# SCH_AP_tempboard_2024-01-17.net
KiCad netlist of a schematic drawn in EasyEDA
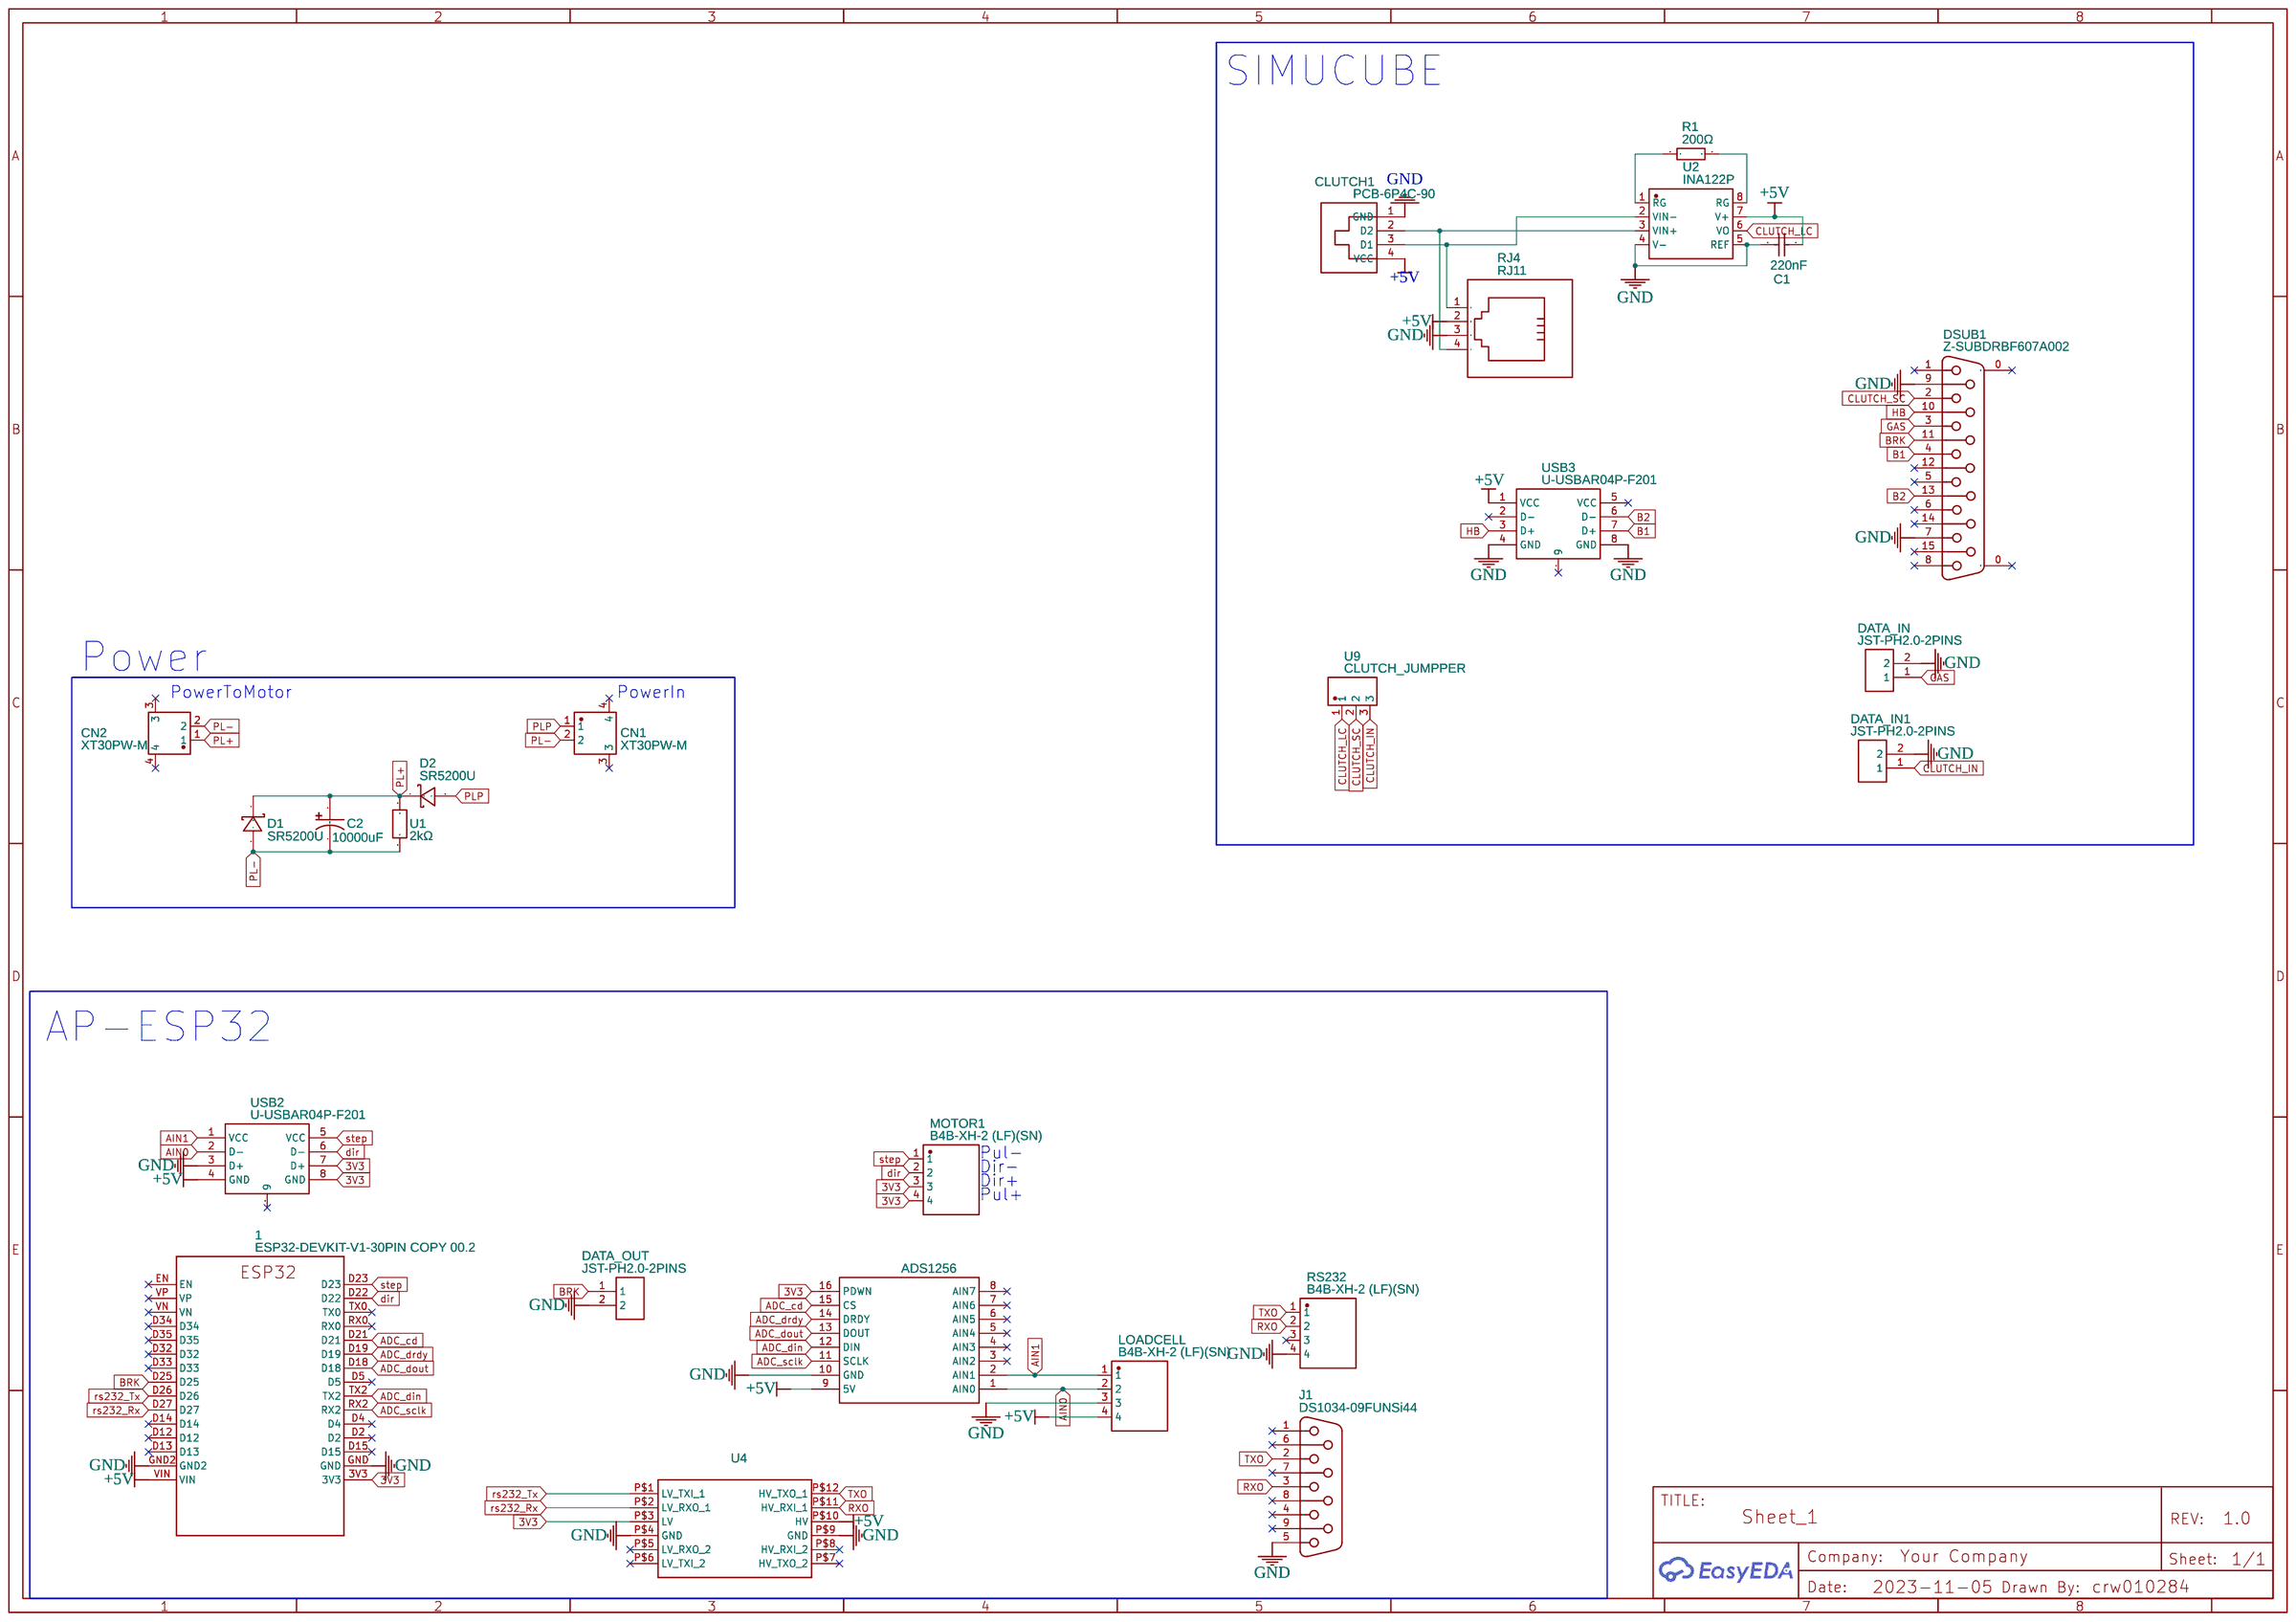
[diagram p0: schematic sheet]

(export (version "E")
  (design (tool "Eeschema 10.0.6"))
  (components
    (comp (ref "1")
      (value "ESP32-DEVKIT-V1-30PIN COPY 00.2")
      (libsource (lib "") (part "ESP32-DEVKIT-V1-30PIN"))
    )
    (comp (ref "C1")
      (value "220nF")
      (fields
        (field (name "Manufacturer Part") "CL10B224KA8NNNC")
        (field (name "Manufacturer") "SAMSUNG(三星)")
      )
      (libsource (lib "") (part "CL10B224KA8NNNC"))
    )
    (comp (ref "C2")
      (value "10000uF")
      (fields (field (name "Manufacturer Part") "HL103M063O510A") (field (name "Manufacturer") "CapXon(丰宾)"))
      (libsource (lib "") (part "HL103M063O510A"))
    )
    (comp (ref "CLUTCH1")
      (value "PCB-6P4C-90")
      (fields (field (name "Manufacturer Part") "R-RJ11R04P-A800") (field (name "Manufacturer") "Ckmtw(灿科盟)"))
      (libsource (lib "") (part "PCB-6P4C-90"))
    )
    (comp (ref "CN1")
      (value "XT30PW-M")
      (fields (field (name "Manufacturer") "AMASS(艾迈斯)"))
      (libsource (lib "") (part "XT30PW-M_1"))
    )
    (comp (ref "CN2")
      (value "XT30PW-M")
      (fields (field (name "Manufacturer") "AMASS(艾迈斯)"))
      (libsource (lib "") (part "XT30PW-M"))
    )
    (comp (ref "D1")
      (value "SR5200U")
      (fields (field (name "Manufacturer") "迪一"))
      (libsource (lib "") (part "SR5200U_1"))
    )
    (comp (ref "D2")
      (value "SR5200U")
      (fields (field (name "Manufacturer") "迪一"))
      (libsource (lib "") (part "SR5200U"))
    )
    (comp (ref "DATA_IN") (value "JST-PH2.0-2PINS") (libsource (lib "") (part "JST-PH2.0-2PINS")))
    (comp (ref "DATA_IN1") (value "JST-PH2.0-2PINS") (libsource (lib "") (part "JST-PH2.0-2PINS")))
    (comp (ref "DATA_OUT") (value "JST-PH2.0-2PINS") (libsource (lib "") (part "JST-PH2.0-2PINS_1")))
    (comp (ref "DSUB1")
      (value "Z-SUBDRBF607A002")
      (fields (field (name "Manufacturer") "Nextron(台湾正凌)"))
      (libsource (lib "") (part "Z-SUBDRBF607A002"))
    )
    (comp (ref "J1")
      (value "DS1034-09FUNSi44")
      (fields (field (name "Manufacturer") "CONNFLY"))
      (libsource (lib "") (part "DS1034-09FUNSi44"))
    )
    (comp (ref "LOADCELL")
      (value "B4B-XH-2 (LF)(SN)")
      (fields (field (name "Manufacturer Part") "B4B-XH-2(LF)(SN)") (field (name "Manufacturer") "JST"))
      (libsource (lib "") (part "B4B-XH-2 (LF)(SN)_2"))
    )
    (comp (ref "MOTOR1")
      (value "B4B-XH-2 (LF)(SN)")
      (fields (field (name "Manufacturer Part") "B4B-XH-2(LF)(SN)") (field (name "Manufacturer") "JST"))
      (libsource (lib "") (part "B4B-XH-2 (LF)(SN)"))
    )
    (comp (ref "R1")
      (value "200Ω")
      (fields
        (field (name "Manufacturer Part") "0402WGF2000TCE")
        (field (name "Manufacturer") "UNI-ROYAL(厚声)")
      )
      (libsource (lib "") (part "0402WGF2000TCE"))
    )
    (comp (ref "RJ4")
      (value "RJ11")
      (fields
        (field (name "Manufacturer Part") "RJII-623K-4P4CGray boundless")
        (field (name "Manufacturer") "ReliaPro")
      )
      (libsource (lib "") (part "RJII-623K-4P4CGray boundless"))
    )
    (comp (ref "RS232")
      (value "B4B-XH-2 (LF)(SN)")
      (fields (field (name "Manufacturer Part") "B4B-XH-2(LF)(SN)") (field (name "Manufacturer") "JST"))
      (libsource (lib "") (part "B4B-XH-2 (LF)(SN)_1"))
    )
    (comp (ref "U1")
      (value "2kΩ")
      (fields (field (name "Manufacturer Part") "RSF5WSJB-91-2K") (field (name "Manufacturer") "YAGEO(国巨)"))
      (libsource (lib "") (part "RSF5WSJB-91-2K"))
    )
    (comp (ref "U2")
      (value "INA122P")
      (fields (field (name "Manufacturer") "TI(德州仪器)"))
      (libsource (lib "") (part "INA122P"))
    )
    (comp (ref "U3") (value "ADS1256") (libsource (lib "") (part "ADS1256")))
    (comp (ref "U4") (value "NO") (libsource (lib "") (part "LOGIC_LEVEL_CONVERTER")))
    (comp (ref "U9")
      (value "CLUTCH_JUMPPER")
      (fields (field (name "Manufacturer Part") "Jumper3"))
      (libsource (lib "") (part "JUMPER3"))
    )
    (comp (ref "USB2")
      (value "U-USBAR04P-F201")
      (fields (field (name "Manufacturer") "Ckmtw(灿科盟)"))
      (libsource (lib "") (part "U-USBAR04P-F201"))
    )
    (comp (ref "USB3")
      (value "U-USBAR04P-F201")
      (fields (field (name "Manufacturer") "Ckmtw(灿科盟)"))
      (libsource (lib "") (part "U-USBAR04P-F201"))
    )
  )
  (nets
    (net (code "1") (name "+5V") (class "Default")
      (node (ref "1") (pin "VIN") (pinfunction "VIN_VIN") (pintype "unspecified"))
      (node (ref "C1") (pin "2") (pinfunction "2_2") (pintype "input"))
      (node (ref "CLUTCH1") (pin "4") (pinfunction "VCC_4") (pintype "unspecified"))
      (node (ref "LOADCELL") (pin "4") (pinfunction "4_4") (pintype "unspecified"))
      (node (ref "RJ4") (pin "2") (pinfunction "2_2") (pintype "unspecified"))
      (node (ref "U2") (pin "7") (pinfunction "V+_7") (pintype "unspecified"))
      (node (ref "U3") (pin "9") (pinfunction "5V_9") (pintype "unspecified"))
      (node (ref "U4") (pin "P$10") (pinfunction "HV_P$10") (pintype "unspecified"))
      (node (ref "USB2") (pin "4") (pinfunction "GND_4") (pintype "unspecified"))
      (node (ref "USB3") (pin "1") (pinfunction "VCC_1") (pintype "unspecified"))
    )
    (net (code "2") (name "3V3") (class "Default")
      (node (ref "1") (pin "3V3") (pinfunction "3V3_3V3") (pintype "unspecified"))
      (node (ref "MOTOR1") (pin "3") (pinfunction "3_3") (pintype "unspecified"))
      (node (ref "MOTOR1") (pin "4") (pinfunction "4_4") (pintype "unspecified"))
      (node (ref "U3") (pin "16") (pinfunction "PDWN_16") (pintype "unspecified"))
      (node (ref "U4") (pin "P$3") (pinfunction "LV_P$3") (pintype "unspecified"))
      (node (ref "USB2") (pin "7") (pinfunction "D+_7") (pintype "unspecified"))
      (node (ref "USB2") (pin "8") (pinfunction "GND_8") (pintype "unspecified"))
    )
    (net (code "3") (name "ADC_cd") (class "Default")
      (node (ref "1") (pin "D21") (pinfunction "D21_D21") (pintype "unspecified"))
      (node (ref "U3") (pin "15") (pinfunction "CS_15") (pintype "unspecified"))
    )
    (net (code "4") (name "ADC_din") (class "Default")
      (node (ref "1") (pin "TX2") (pinfunction "TX2_TX2") (pintype "unspecified"))
      (node (ref "U3") (pin "12") (pinfunction "DIN_12") (pintype "unspecified"))
    )
    (net (code "5") (name "ADC_dout") (class "Default")
      (node (ref "1") (pin "D18") (pinfunction "D18_D18") (pintype "unspecified"))
      (node (ref "U3") (pin "13") (pinfunction "DOUT_13") (pintype "unspecified"))
    )
    (net (code "6") (name "ADC_drdy") (class "Default")
      (node (ref "1") (pin "D19") (pinfunction "D19_D19") (pintype "unspecified"))
      (node (ref "U3") (pin "14") (pinfunction "DRDY_14") (pintype "unspecified"))
    )
    (net (code "7") (name "ADC_sclk") (class "Default")
      (node (ref "1") (pin "RX2") (pinfunction "RX2_RX2") (pintype "unspecified"))
      (node (ref "U3") (pin "11") (pinfunction "SCLK_11") (pintype "unspecified"))
    )
    (net (code "8") (name "AIN0") (class "Default")
      (node (ref "LOADCELL") (pin "2") (pinfunction "2_2") (pintype "unspecified"))
      (node (ref "U3") (pin "1") (pinfunction "AIN0_1") (pintype "unspecified"))
      (node (ref "USB2") (pin "2") (pinfunction "D-_2") (pintype "unspecified"))
    )
    (net (code "9") (name "AIN1") (class "Default")
      (node (ref "LOADCELL") (pin "1") (pinfunction "1_1") (pintype "unspecified"))
      (node (ref "U3") (pin "2") (pinfunction "AIN1_2") (pintype "unspecified"))
      (node (ref "USB2") (pin "1") (pinfunction "VCC_1") (pintype "unspecified"))
    )
    (net (code "10") (name "B1") (class "Default")
      (node (ref "DSUB1") (pin "4") (pinfunction "4_4") (pintype "input"))
      (node (ref "USB3") (pin "7") (pinfunction "D+_7") (pintype "unspecified"))
    )
    (net (code "11") (name "B2") (class "Default")
      (node (ref "DSUB1") (pin "13") (pinfunction "13_13") (pintype "input"))
      (node (ref "USB3") (pin "6") (pinfunction "D-_6") (pintype "unspecified"))
    )
    (net (code "12") (name "BRK") (class "Default")
      (node (ref "1") (pin "D25") (pinfunction "D25_D25") (pintype "unspecified"))
      (node (ref "DATA_OUT") (pin "1") (pinfunction "1_1") (pintype "unspecified"))
      (node (ref "DSUB1") (pin "11") (pinfunction "11_11") (pintype "input"))
    )
    (net (code "13") (name "CLUTCH_IN") (class "Default")
      (node (ref "DATA_IN1") (pin "1") (pinfunction "1_1") (pintype "unspecified"))
      (node (ref "U9") (pin "3") (pinfunction "3_3") (pintype "unspecified"))
    )
    (net (code "14") (name "CLUTCH_LC") (class "Default")
      (node (ref "U2") (pin "6") (pinfunction "VO_6") (pintype "unspecified"))
      (node (ref "U9") (pin "1") (pinfunction "1_1") (pintype "unspecified"))
    )
    (net (code "15") (name "CLUTCH_SC") (class "Default")
      (node (ref "DSUB1") (pin "2") (pinfunction "2_2") (pintype "input"))
      (node (ref "U9") (pin "2") (pinfunction "2_2") (pintype "unspecified"))
    )
    (net (code "16") (name "GAS") (class "Default")
      (node (ref "DATA_IN") (pin "1") (pinfunction "1_1") (pintype "unspecified"))
      (node (ref "DSUB1") (pin "3") (pinfunction "3_3") (pintype "input"))
    )
    (net (code "17") (name "GND") (class "Default")
      (node (ref "1") (pin "GND") (pinfunction "GND_GND") (pintype "unspecified"))
      (node (ref "1") (pin "GND2") (pinfunction "GND2_GND2") (pintype "unspecified"))
      (node (ref "C1") (pin "1") (pinfunction "1_1") (pintype "input"))
      (node (ref "CLUTCH1") (pin "1") (pinfunction "GND_1") (pintype "unspecified"))
      (node (ref "DATA_IN") (pin "2") (pinfunction "2_2") (pintype "unspecified"))
      (node (ref "DATA_IN1") (pin "2") (pinfunction "2_2") (pintype "unspecified"))
      (node (ref "DATA_OUT") (pin "2") (pinfunction "2_2") (pintype "unspecified"))
      (node (ref "DSUB1") (pin "7") (pinfunction "7_7") (pintype "input"))
      (node (ref "DSUB1") (pin "9") (pinfunction "9_9") (pintype "input"))
      (node (ref "J1") (pin "5") (pinfunction "5_5") (pintype "unspecified"))
      (node (ref "LOADCELL") (pin "3") (pinfunction "3_3") (pintype "unspecified"))
      (node (ref "RJ4") (pin "3") (pinfunction "3_3") (pintype "unspecified"))
      (node (ref "RS232") (pin "4") (pinfunction "4_4") (pintype "unspecified"))
      (node (ref "U2") (pin "4") (pinfunction "V-_4") (pintype "unspecified"))
      (node (ref "U2") (pin "5") (pinfunction "REF_5") (pintype "unspecified"))
      (node (ref "U3") (pin "10") (pinfunction "GND_10") (pintype "unspecified"))
      (node (ref "U4") (pin "P$4") (pinfunction "GND_P$4") (pintype "unspecified"))
      (node (ref "U4") (pin "P$9") (pinfunction "GND_P$9") (pintype "unspecified"))
      (node (ref "USB2") (pin "3") (pinfunction "D+_3") (pintype "unspecified"))
      (node (ref "USB3") (pin "4") (pinfunction "GND_4") (pintype "unspecified"))
      (node (ref "USB3") (pin "8") (pinfunction "GND_8") (pintype "unspecified"))
    )
    (net (code "18") (name "HB") (class "Default")
      (node (ref "DSUB1") (pin "10") (pinfunction "10_10") (pintype "input"))
      (node (ref "USB3") (pin "3") (pinfunction "D+_3") (pintype "unspecified"))
    )
    (net (code "19") (name "Net-(CLUTCH1-D1)") (class "Default")
      (node (ref "CLUTCH1") (pin "3") (pinfunction "D1_3") (pintype "unspecified"))
      (node (ref "RJ4") (pin "1") (pinfunction "1_1") (pintype "unspecified"))
      (node (ref "U2") (pin "2") (pinfunction "VIN-_2") (pintype "unspecified"))
    )
    (net (code "20") (name "Net-(CLUTCH1-D2)") (class "Default")
      (node (ref "CLUTCH1") (pin "2") (pinfunction "D2_2") (pintype "unspecified"))
      (node (ref "RJ4") (pin "4") (pinfunction "4_4") (pintype "unspecified"))
      (node (ref "U2") (pin "3") (pinfunction "VIN+_3") (pintype "unspecified"))
    )
    (net (code "21") (name "Net-(R1-Pad1)") (class "Default")
      (node (ref "R1") (pin "1") (pinfunction "1_1") (pintype "input"))
      (node (ref "U2") (pin "1") (pinfunction "RG_1") (pintype "unspecified"))
    )
    (net (code "22") (name "Net-(R1-Pad2)") (class "Default")
      (node (ref "R1") (pin "2") (pinfunction "2_2") (pintype "input"))
      (node (ref "U2") (pin "8") (pinfunction "RG_8") (pintype "unspecified"))
    )
    (net (code "23") (name "PL+") (class "Default")
      (node (ref "C2") (pin "1") (pinfunction "1_1") (pintype "unspecified"))
      (node (ref "CN2") (pin "1") (pinfunction "1_1") (pintype "unspecified"))
      (node (ref "D1") (pin "1") (pinfunction "C_1") (pintype "unspecified"))
      (node (ref "D2") (pin "1") (pinfunction "C_1") (pintype "unspecified"))
      (node (ref "U1") (pin "1") (pinfunction "1_1") (pintype "unspecified"))
    )
    (net (code "24") (name "PL-") (class "Default")
      (node (ref "C2") (pin "2") (pinfunction "2_2") (pintype "unspecified"))
      (node (ref "CN1") (pin "2") (pinfunction "2_2") (pintype "unspecified"))
      (node (ref "CN2") (pin "2") (pinfunction "2_2") (pintype "unspecified"))
      (node (ref "D1") (pin "2") (pinfunction "A_2") (pintype "unspecified"))
      (node (ref "U1") (pin "2") (pinfunction "2_2") (pintype "unspecified"))
    )
    (net (code "25") (name "PLP") (class "Default")
      (node (ref "CN1") (pin "1") (pinfunction "1_1") (pintype "unspecified"))
      (node (ref "D2") (pin "2") (pinfunction "A_2") (pintype "unspecified"))
    )
    (net (code "26") (name "RXO") (class "Default")
      (node (ref "J1") (pin "3") (pinfunction "3_3") (pintype "unspecified"))
      (node (ref "RS232") (pin "2") (pinfunction "2_2") (pintype "unspecified"))
      (node (ref "U4") (pin "P$11") (pinfunction "HV_RXI_1_P$11") (pintype "unspecified"))
    )
    (net (code "27") (name "TXO") (class "Default")
      (node (ref "J1") (pin "2") (pinfunction "2_2") (pintype "unspecified"))
      (node (ref "RS232") (pin "1") (pinfunction "1_1") (pintype "unspecified"))
      (node (ref "U4") (pin "P$12") (pinfunction "HV_TXO_1_P$12") (pintype "unspecified"))
    )
    (net (code "28") (name "dir") (class "Default")
      (node (ref "1") (pin "D22") (pinfunction "D22_D22") (pintype "unspecified"))
      (node (ref "MOTOR1") (pin "2") (pinfunction "2_2") (pintype "unspecified"))
      (node (ref "USB2") (pin "6") (pinfunction "D-_6") (pintype "unspecified"))
    )
    (net (code "29") (name "rs232_Rx") (class "Default")
      (node (ref "1") (pin "D27") (pinfunction "D27_D27") (pintype "unspecified"))
      (node (ref "U4") (pin "P$2") (pinfunction "LV_RXO_1_P$2") (pintype "unspecified"))
    )
    (net (code "30") (name "rs232_Tx") (class "Default")
      (node (ref "1") (pin "D26") (pinfunction "D26_D26") (pintype "unspecified"))
      (node (ref "U4") (pin "P$1") (pinfunction "LV_TXI_1_P$1") (pintype "unspecified"))
    )
    (net (code "31") (name "step") (class "Default")
      (node (ref "1") (pin "D23") (pinfunction "D23_D23") (pintype "unspecified"))
      (node (ref "MOTOR1") (pin "1") (pinfunction "1_1") (pintype "unspecified"))
      (node (ref "USB2") (pin "5") (pinfunction "VCC_5") (pintype "unspecified"))
    )
    (net (code "32") (name "unconnected-(1-PadD2)") (class "Default")
      (node (ref "1") (pin "D2") (pinfunction "D2_D2") (pintype "unspecified+no_connect"))
    )
    (net (code "33") (name "unconnected-(1-PadD4)") (class "Default")
      (node (ref "1") (pin "D4") (pinfunction "D4_D4") (pintype "unspecified+no_connect"))
    )
    (net (code "34") (name "unconnected-(1-PadD5)") (class "Default")
      (node (ref "1") (pin "D5") (pinfunction "D5_D5") (pintype "unspecified+no_connect"))
    )
    (net (code "35") (name "unconnected-(1-PadD12)") (class "Default")
      (node (ref "1") (pin "D12") (pinfunction "D12_D12") (pintype "unspecified+no_connect"))
    )
    (net (code "36") (name "unconnected-(1-PadD13)") (class "Default")
      (node (ref "1") (pin "D13") (pinfunction "D13_D13") (pintype "unspecified+no_connect"))
    )
    (net (code "37") (name "unconnected-(1-PadD14)") (class "Default")
      (node (ref "1") (pin "D14") (pinfunction "D14_D14") (pintype "unspecified+no_connect"))
    )
    (net (code "38") (name "unconnected-(1-PadD15)") (class "Default")
      (node (ref "1") (pin "D15") (pinfunction "D15_D15") (pintype "unspecified+no_connect"))
    )
    (net (code "39") (name "unconnected-(1-PadD32)") (class "Default")
      (node (ref "1") (pin "D32") (pinfunction "D32_D32") (pintype "unspecified+no_connect"))
    )
    (net (code "40") (name "unconnected-(1-PadD33)") (class "Default")
      (node (ref "1") (pin "D33") (pinfunction "D33_D33") (pintype "unspecified+no_connect"))
    )
    (net (code "41") (name "unconnected-(1-PadD34)") (class "Default")
      (node (ref "1") (pin "D34") (pinfunction "D34_D34") (pintype "unspecified+no_connect"))
    )
    (net (code "42") (name "unconnected-(1-PadD35)") (class "Default")
      (node (ref "1") (pin "D35") (pinfunction "D35_D35") (pintype "unspecified+no_connect"))
    )
    (net (code "43") (name "unconnected-(1-PadEN)") (class "Default")
      (node (ref "1") (pin "EN") (pinfunction "EN_EN") (pintype "unspecified+no_connect"))
    )
    (net (code "44") (name "unconnected-(1-PadRX0)") (class "Default")
      (node (ref "1") (pin "RX0") (pinfunction "RX0_RX0") (pintype "unspecified+no_connect"))
    )
    (net (code "45") (name "unconnected-(1-PadTX0)") (class "Default")
      (node (ref "1") (pin "TX0") (pinfunction "TX0_TX0") (pintype "unspecified+no_connect"))
    )
    (net (code "46") (name "unconnected-(1-PadVN)") (class "Default")
      (node (ref "1") (pin "VN") (pinfunction "VN_VN") (pintype "unspecified+no_connect"))
    )
    (net (code "47") (name "unconnected-(1-PadVP)") (class "Default")
      (node (ref "1") (pin "VP") (pinfunction "VP_VP") (pintype "unspecified+no_connect"))
    )
    (net (code "48") (name "unconnected-(CN1-Pad3)") (class "Default")
      (node (ref "CN1") (pin "3") (pinfunction "3_3") (pintype "unspecified+no_connect"))
    )
    (net (code "49") (name "unconnected-(CN1-Pad4)") (class "Default")
      (node (ref "CN1") (pin "4") (pinfunction "4_4") (pintype "unspecified+no_connect"))
    )
    (net (code "50") (name "unconnected-(CN2-Pad3)") (class "Default")
      (node (ref "CN2") (pin "3") (pinfunction "3_3") (pintype "unspecified+no_connect"))
    )
    (net (code "51") (name "unconnected-(CN2-Pad4)") (class "Default")
      (node (ref "CN2") (pin "4") (pinfunction "4_4") (pintype "unspecified+no_connect"))
    )
    (net (code "52") (name "unconnected-(DSUB1-MH1-Pad0)") (class "Default")
      (node (ref "DSUB1") (pin "0") (pinfunction "MH1_0") (pintype "input+no_connect"))
    )
    (net (code "53") (name "unconnected-(DSUB1-MH2-Pad0)") (class "Default")
      (node (ref "DSUB1") (pin "0") (pinfunction "MH2_0") (pintype "input+no_connect"))
    )
    (net (code "54") (name "unconnected-(DSUB1-Pad1)") (class "Default")
      (node (ref "DSUB1") (pin "1") (pinfunction "1_1") (pintype "input+no_connect"))
    )
    (net (code "55") (name "unconnected-(DSUB1-Pad5)") (class "Default")
      (node (ref "DSUB1") (pin "5") (pinfunction "5_5") (pintype "input+no_connect"))
    )
    (net (code "56") (name "unconnected-(DSUB1-Pad6)") (class "Default")
      (node (ref "DSUB1") (pin "6") (pinfunction "6_6") (pintype "input+no_connect"))
    )
    (net (code "57") (name "unconnected-(DSUB1-Pad8)") (class "Default")
      (node (ref "DSUB1") (pin "8") (pinfunction "8_8") (pintype "input+no_connect"))
    )
    (net (code "58") (name "unconnected-(DSUB1-Pad12)") (class "Default")
      (node (ref "DSUB1") (pin "12") (pinfunction "12_12") (pintype "input+no_connect"))
    )
    (net (code "59") (name "unconnected-(DSUB1-Pad14)") (class "Default")
      (node (ref "DSUB1") (pin "14") (pinfunction "14_14") (pintype "input+no_connect"))
    )
    (net (code "60") (name "unconnected-(DSUB1-Pad15)") (class "Default")
      (node (ref "DSUB1") (pin "15") (pinfunction "15_15") (pintype "input+no_connect"))
    )
    (net (code "61") (name "unconnected-(J1-Pad1)") (class "Default")
      (node (ref "J1") (pin "1") (pinfunction "1_1") (pintype "unspecified+no_connect"))
    )
    (net (code "62") (name "unconnected-(J1-Pad4)") (class "Default")
      (node (ref "J1") (pin "4") (pinfunction "4_4") (pintype "unspecified+no_connect"))
    )
    (net (code "63") (name "unconnected-(J1-Pad6)") (class "Default")
      (node (ref "J1") (pin "6") (pinfunction "6_6") (pintype "unspecified+no_connect"))
    )
    (net (code "64") (name "unconnected-(J1-Pad7)") (class "Default")
      (node (ref "J1") (pin "7") (pinfunction "7_7") (pintype "unspecified+no_connect"))
    )
    (net (code "65") (name "unconnected-(J1-Pad8)") (class "Default")
      (node (ref "J1") (pin "8") (pinfunction "8_8") (pintype "unspecified+no_connect"))
    )
    (net (code "66") (name "unconnected-(J1-Pad9)") (class "Default")
      (node (ref "J1") (pin "9") (pinfunction "9_9") (pintype "unspecified+no_connect"))
    )
    (net (code "67") (name "unconnected-(RS232-Pad3)") (class "Default")
      (node (ref "RS232") (pin "3") (pinfunction "3_3") (pintype "unspecified+no_connect"))
    )
    (net (code "68") (name "unconnected-(U3-AIN2-Pad3)") (class "Default")
      (node (ref "U3") (pin "3") (pinfunction "AIN2_3") (pintype "unspecified+no_connect"))
    )
    (net (code "69") (name "unconnected-(U3-AIN3-Pad4)") (class "Default")
      (node (ref "U3") (pin "4") (pinfunction "AIN3_4") (pintype "unspecified+no_connect"))
    )
    (net (code "70") (name "unconnected-(U3-AIN4-Pad5)") (class "Default")
      (node (ref "U3") (pin "5") (pinfunction "AIN4_5") (pintype "unspecified+no_connect"))
    )
    (net (code "71") (name "unconnected-(U3-AIN5-Pad6)") (class "Default")
      (node (ref "U3") (pin "6") (pinfunction "AIN5_6") (pintype "unspecified+no_connect"))
    )
    (net (code "72") (name "unconnected-(U3-AIN6-Pad7)") (class "Default")
      (node (ref "U3") (pin "7") (pinfunction "AIN6_7") (pintype "unspecified+no_connect"))
    )
    (net (code "73") (name "unconnected-(U3-AIN7-Pad8)") (class "Default")
      (node (ref "U3") (pin "8") (pinfunction "AIN7_8") (pintype "unspecified+no_connect"))
    )
    (net (code "74") (name "unconnected-(U4-HV_RXI_2-PadP$8)") (class "Default")
      (node (ref "U4") (pin "P$8") (pinfunction "HV_RXI_2_P$8") (pintype "unspecified+no_connect"))
    )
    (net (code "75") (name "unconnected-(U4-HV_TXO_2-PadP$7)") (class "Default")
      (node (ref "U4") (pin "P$7") (pinfunction "HV_TXO_2_P$7") (pintype "unspecified+no_connect"))
    )
    (net (code "76") (name "unconnected-(U4-LV_RXO_2-PadP$5)") (class "Default")
      (node (ref "U4") (pin "P$5") (pinfunction "LV_RXO_2_P$5") (pintype "unspecified+no_connect"))
    )
    (net (code "77") (name "unconnected-(U4-LV_TXI_2-PadP$6)") (class "Default")
      (node (ref "U4") (pin "P$6") (pinfunction "LV_TXI_2_P$6") (pintype "unspecified+no_connect"))
    )
    (net (code "78") (name "unconnected-(USB2-Pad9)") (class "Default")
      (node (ref "USB2") (pin "9") (pinfunction "9_9") (pintype "unspecified+no_connect"))
    )
    (net (code "79") (name "unconnected-(USB3-D--Pad2)") (class "Default")
      (node (ref "USB3") (pin "2") (pinfunction "D-_2") (pintype "unspecified+no_connect"))
    )
    (net (code "80") (name "unconnected-(USB3-Pad9)") (class "Default")
      (node (ref "USB3") (pin "9") (pinfunction "9_9") (pintype "unspecified+no_connect"))
    )
    (net (code "81") (name "unconnected-(USB3-VCC-Pad5)") (class "Default")
      (node (ref "USB3") (pin "5") (pinfunction "VCC_5") (pintype "unspecified+no_connect"))
    )
  )
)
